# 2024-4T-MNT-2.net
KiCad netlist of a schematic drawn in EasyEDA Pro
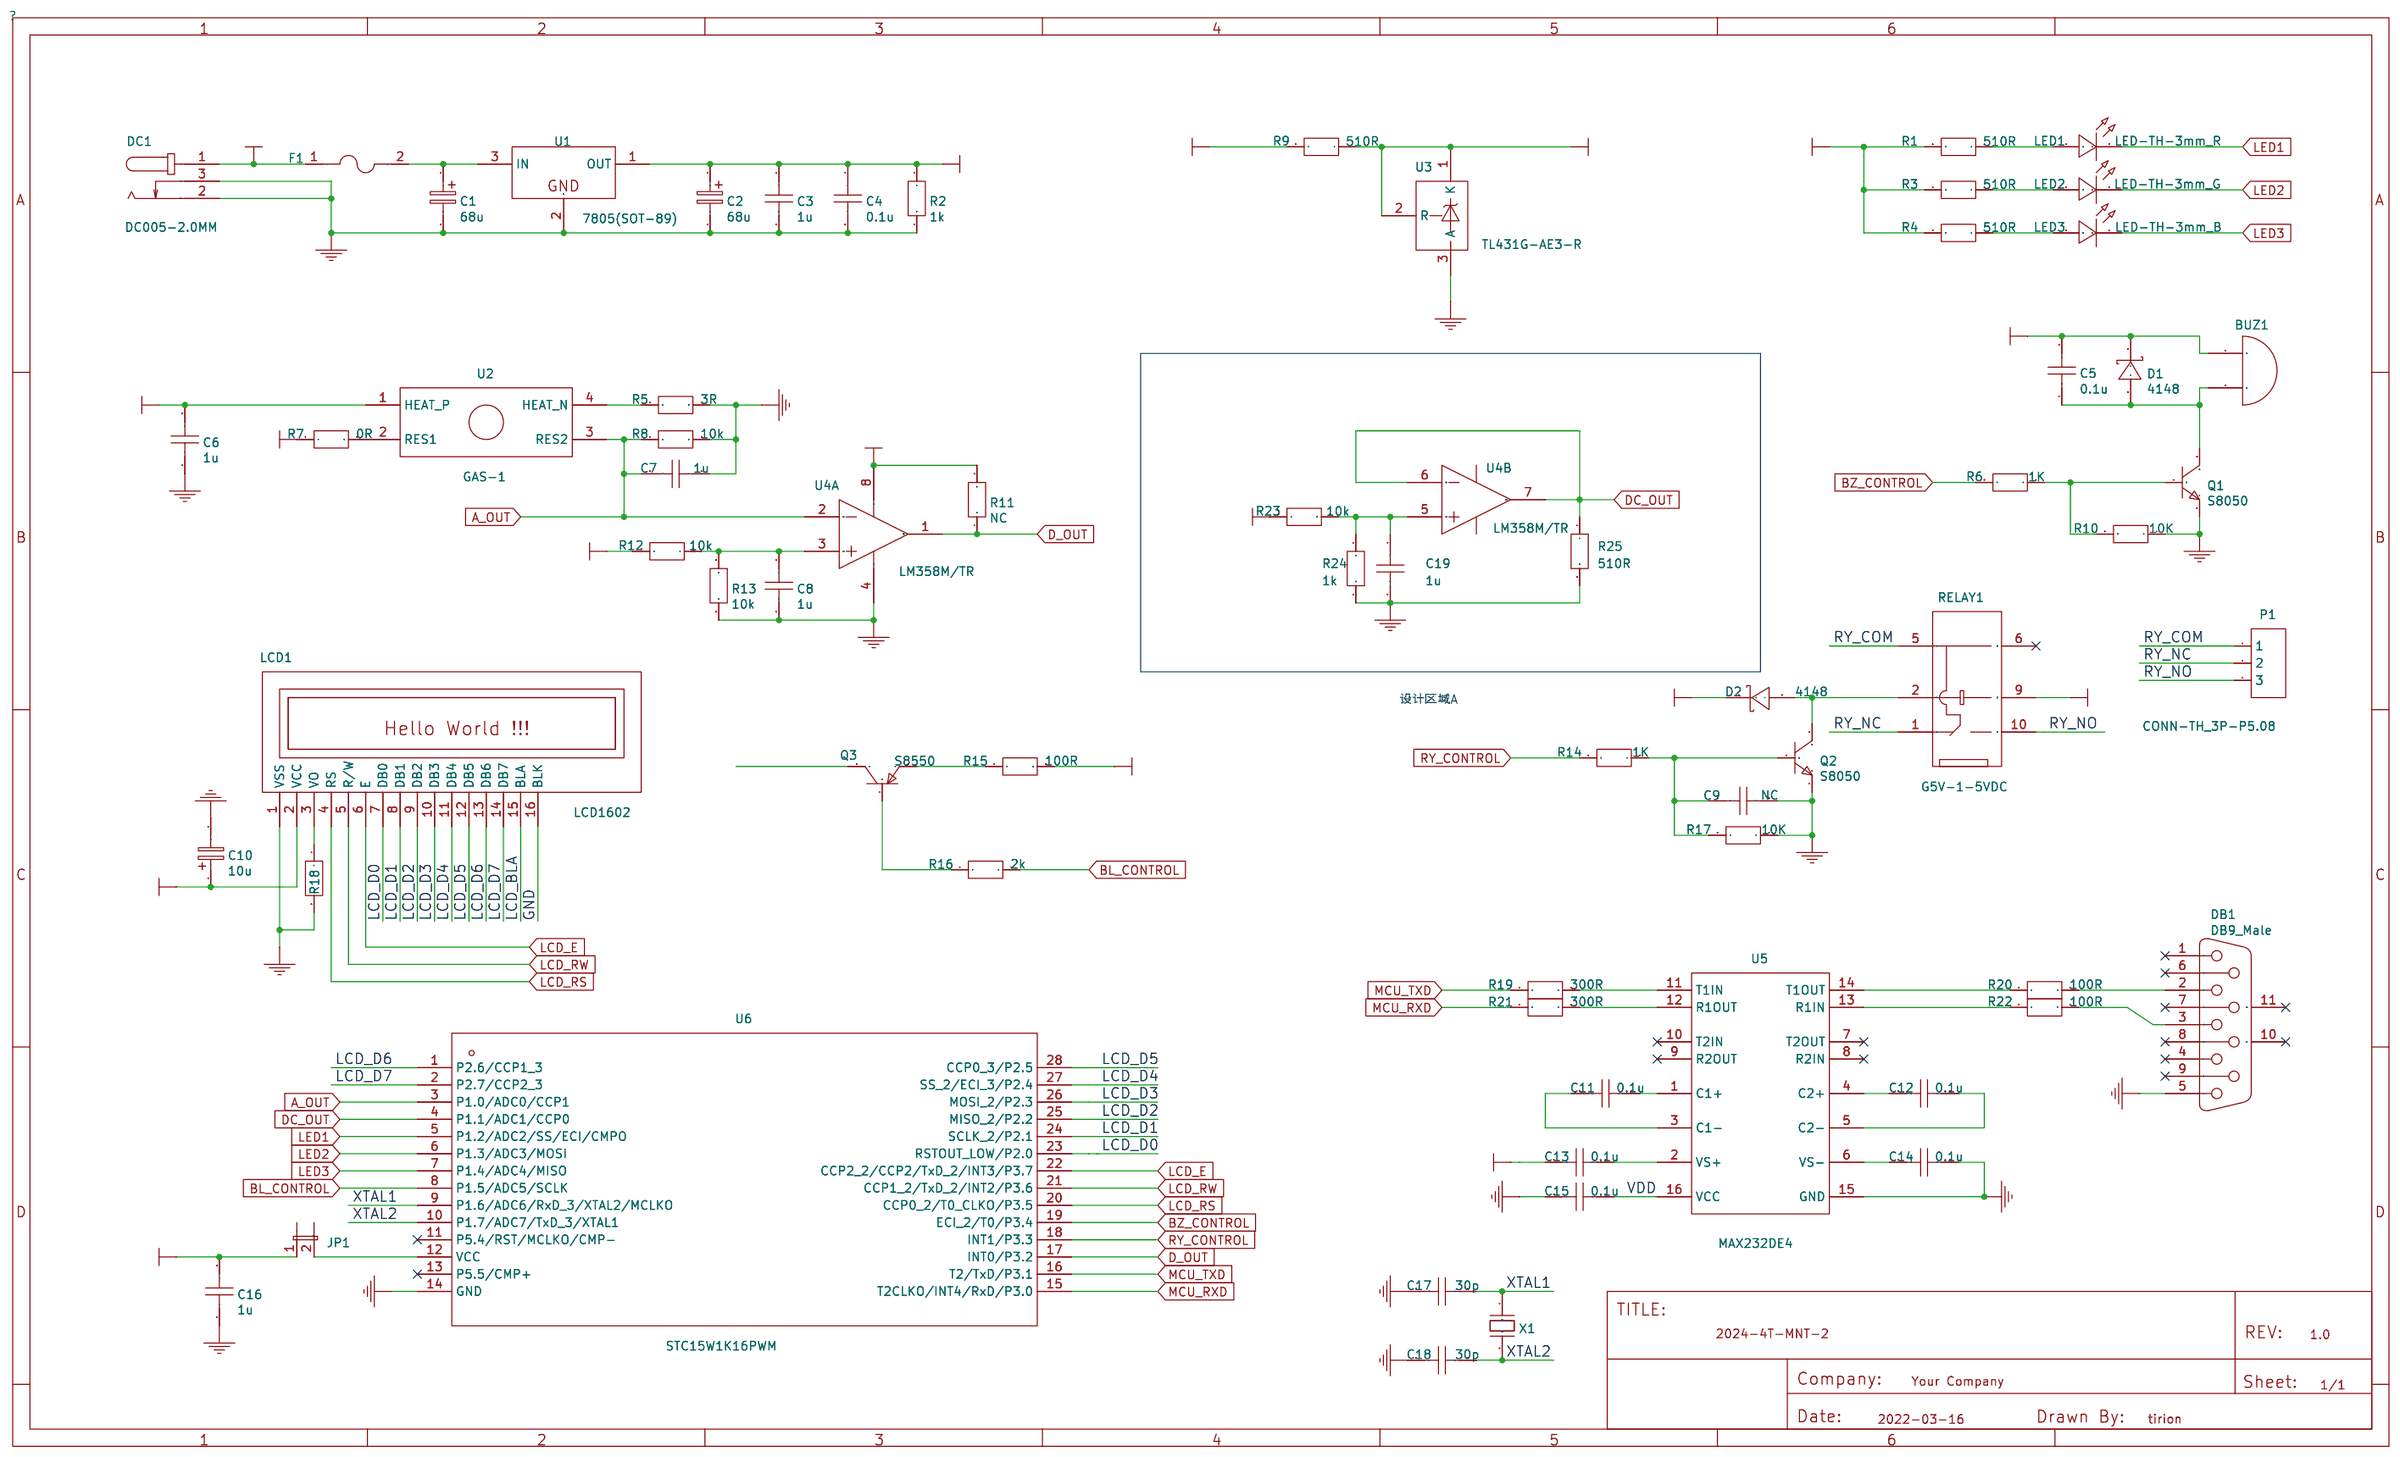
[diagram p0: schematic sheet]

(export (version "E")
  (design (tool "Eeschema 10.0.6"))
  (components
    (comp (ref "BUZ1") (value "BUZ1") (libsource (lib "easyedapro") (part "BUZ1")))
    (comp (ref "C1") (value "68u") (libsource (lib "easyedapro") (part "68u")))
    (comp (ref "C2") (value "68u") (libsource (lib "easyedapro") (part "68u")))
    (comp (ref "C3") (value "1u") (libsource (lib "easyedapro") (part "1u")))
    (comp (ref "C4") (value "0.1u") (libsource (lib "easyedapro") (part "0.1u")))
    (comp (ref "C5") (value "0.1u") (libsource (lib "easyedapro") (part "0.1u")))
    (comp (ref "C6") (value "1u") (libsource (lib "easyedapro") (part "1u")))
    (comp (ref "C7") (value "1u") (libsource (lib "easyedapro") (part "1u")))
    (comp (ref "C8") (value "1u") (libsource (lib "easyedapro") (part "1u")))
    (comp (ref "C9") (value "NC") (libsource (lib "") (part "NC_1")))
    (comp (ref "C10") (value "10u") (libsource (lib "easyedapro") (part "10u")))
    (comp (ref "C11") (value "0.1u") (libsource (lib "easyedapro") (part "0.1u")))
    (comp (ref "C12") (value "0.1u") (libsource (lib "easyedapro") (part "0.1u")))
    (comp (ref "C13") (value "0.1u") (libsource (lib "easyedapro") (part "0.1u")))
    (comp (ref "C14") (value "0.1u") (libsource (lib "easyedapro") (part "0.1u")))
    (comp (ref "C15") (value "0.1u") (libsource (lib "easyedapro") (part "0.1u")))
    (comp (ref "C16") (value "1u") (libsource (lib "easyedapro") (part "1u")))
    (comp (ref "C17") (value "30p") (libsource (lib "easyedapro") (part "30p")))
    (comp (ref "C18") (value "30p") (libsource (lib "easyedapro") (part "30p")))
    (comp (ref "C19") (value "1u") (libsource (lib "easyedapro") (part "1u")))
    (comp (ref "D1")
      (value "4148")
      (fields (field (name "Manufacturer Part") "SS14") (field (name "Manufacturer") "MDD"))
      (libsource (lib "easyedapro") (part "4148"))
    )
    (comp (ref "D2")
      (value "4148")
      (fields (field (name "Manufacturer Part") "SS14") (field (name "Manufacturer") "MDD"))
      (libsource (lib "easyedapro") (part "4148"))
    )
    (comp (ref "DB1")
      (value "DB9_Male")
      (fields (field (name "Manufacturer") "Amphenol"))
      (libsource (lib "easyedapro") (part "DB9_Male"))
    )
    (comp (ref "DC1")
      (value "DC005-2.0MM")
      (fields (field (name "Manufacturer") "SOFNG"))
      (libsource (lib "easyedapro") (part "DC005-2.0MM"))
    )
    (comp (ref "F1") (value "FUSE_F1812_FUSE") (libsource (lib "easyedapro") (part "FUSE_F1812_FUSE")))
    (comp (ref "JP1") (value "JUMPER2") (libsource (lib "easyedapro") (part "JUMPER2")))
    (comp (ref "LCD1")
      (value "LCD1602")
      (fields
        (field (name "Manufacturer Part") "LCM1602K-NSW-BBW")
        (field (name "Manufacturer") "LONTECH(厦门龙特)")
      )
      (libsource (lib "easyedapro") (part "LCD1602"))
    )
    (comp (ref "LED1")
      (value "LED-TH-3mm_R")
      (fields
        (field (name "Manufacturer Part") "204-10SDRD/S530-A3-L")
        (field (name "Manufacturer") "EVERLIGHT(台湾亿光)")
      )
      (libsource (lib "easyedapro") (part "LED-TH-3mm_R"))
    )
    (comp (ref "LED2")
      (value "LED-TH-3mm_G")
      (fields
        (field (name "Manufacturer Part") "204-10SYGD/S530-E3")
        (field (name "Manufacturer") "EVERLIGHT(台湾亿光)")
      )
      (libsource (lib "easyedapro") (part "LED-TH-3mm_G"))
    )
    (comp (ref "LED3")
      (value "LED-TH-3mm_B")
      (fields
        (field (name "Manufacturer Part") "204-10SUBC/S400-A4")
        (field (name "Manufacturer") "EVERLIGHT(台湾亿光)")
      )
      (libsource (lib "easyedapro") (part "LED-TH-3mm_B"))
    )
    (comp (ref "P1") (value "CONN-TH_3P-P5.08") (libsource (lib "easyedapro") (part "CONN-TH_3P-P5.08")))
    (comp (ref "Q1")
      (value "S8050")
      (fields (field (name "Manufacturer") "JSMSEMI"))
      (libsource (lib "easyedapro") (part "S8050"))
    )
    (comp (ref "Q2")
      (value "S8050")
      (fields (field (name "Manufacturer") "JSMSEMI"))
      (libsource (lib "easyedapro") (part "S8050"))
    )
    (comp (ref "Q3")
      (value "S8550")
      (fields
        (field (name "Manufacturer Part") "S8550-H")
        (field (name "Manufacturer") "Yangzhou Yangjie Elec Tech")
      )
      (libsource (lib "easyedapro") (part "S8550"))
    )
    (comp (ref "R1") (value "510R") (libsource (lib "easyedapro") (part "510R")))
    (comp (ref "R2") (value "1k") (libsource (lib "easyedapro") (part "1k")))
    (comp (ref "R3") (value "510R") (libsource (lib "easyedapro") (part "510R")))
    (comp (ref "R4") (value "510R") (libsource (lib "easyedapro") (part "510R")))
    (comp (ref "R5") (value "3R") (libsource (lib "easyedapro") (part "3R")))
    (comp (ref "R6") (value "1K") (libsource (lib "easyedapro") (part "1K")))
    (comp (ref "R7") (value "0R") (libsource (lib "easyedapro") (part "0R")))
    (comp (ref "R8") (value "10k") (libsource (lib "easyedapro") (part "10k")))
    (comp (ref "R9") (value "510R") (libsource (lib "easyedapro") (part "510R")))
    (comp (ref "R10") (value "10K") (libsource (lib "easyedapro") (part "10K")))
    (comp (ref "R11") (value "NC") (libsource (lib "easyedapro") (part "NC")))
    (comp (ref "R12") (value "10k") (libsource (lib "easyedapro") (part "10k")))
    (comp (ref "R13") (value "10k") (libsource (lib "easyedapro") (part "10k")))
    (comp (ref "R14") (value "1K") (libsource (lib "easyedapro") (part "1K")))
    (comp (ref "R15") (value "100R") (libsource (lib "easyedapro") (part "100R")))
    (comp (ref "R16") (value "2k") (libsource (lib "easyedapro") (part "2k")))
    (comp (ref "R17") (value "10K") (libsource (lib "easyedapro") (part "10K")))
    (comp (ref "R18") (value "10k") (libsource (lib "easyedapro") (part "10k")))
    (comp (ref "R19") (value "300R") (libsource (lib "easyedapro") (part "300R")))
    (comp (ref "R20") (value "100R") (libsource (lib "easyedapro") (part "100R")))
    (comp (ref "R21") (value "300R") (libsource (lib "easyedapro") (part "300R")))
    (comp (ref "R22") (value "100R") (libsource (lib "easyedapro") (part "100R")))
    (comp (ref "R23") (value "10k") (libsource (lib "easyedapro") (part "10k")))
    (comp (ref "R24") (value "1k") (libsource (lib "easyedapro") (part "1k")))
    (comp (ref "R25") (value "510R") (libsource (lib "easyedapro") (part "510R")))
    (comp (ref "RELAY1")
      (value "G5V-1-5VDC")
      (fields (field (name "Manufacturer") "OMRON"))
      (libsource (lib "easyedapro") (part "G5V-1-5VDC"))
    )
    (comp (ref "U1")
      (value "7805(SOT-89)")
      (fields (field (name "Manufacturer Part") "CJ78L05") (field (name "Manufacturer") "CJ"))
      (libsource (lib "easyedapro") (part "7805(SOT-89)"))
    )
    (comp (ref "U2") (value "GAS-1") (libsource (lib "easyedapro") (part "GAS-1")))
    (comp (ref "U3")
      (value "TL431G-AE3-R")
      (fields (field (name "Manufacturer") "UTC"))
      (libsource (lib "easyedapro") (part "TL431G-AE3-R"))
    )
    (comp (ref "U4")
      (value "LM358M/TR")
      (fields (field (name "Manufacturer") "HGSEMI"))
      (libsource (lib "easyedapro") (part "LM358M/TR"))
    )
    (comp (ref "U5") (value "MAX232DE4") (libsource (lib "easyedapro") (part "MAX232DE4")))
    (comp (ref "U6")
      (value "STC15W1K16PWM")
      (fields (field (name "Manufacturer") "STC"))
      (libsource (lib "easyedapro") (part "STC15W1K16PWM"))
    )
    (comp (ref "X1")
      (value "12MHZ")
      (fields (field (name "Manufacturer Part") "X49UD12MSD2SC") (field (name "Manufacturer") "LCSC"))
      (libsource (lib "easyedapro") (part "12MHZ"))
    )
  )
  (nets
    (net (code "1") (name "/LCD_BLA") (class "Default")
      (node (ref "LCD1") (pin "15") (pinfunction "BLA_15") (pintype "input"))
    )
    (net (code "2") (name "/LCD_D0") (class "Default")
      (node (ref "LCD1") (pin "7") (pinfunction "DB0_7") (pintype "input"))
      (node (ref "U6") (pin "23") (pinfunction "RSTOUT_LOW/P2.0_23") (pintype "input"))
    )
    (net (code "3") (name "/LCD_D1") (class "Default")
      (node (ref "LCD1") (pin "8") (pinfunction "DB1_8") (pintype "input"))
      (node (ref "U6") (pin "24") (pinfunction "SCLK_2/P2.1_24") (pintype "input"))
    )
    (net (code "4") (name "/LCD_D2") (class "Default")
      (node (ref "LCD1") (pin "9") (pinfunction "DB2_9") (pintype "input"))
      (node (ref "U6") (pin "25") (pinfunction "MISO_2/P2.2_25") (pintype "input"))
    )
    (net (code "5") (name "/LCD_D3") (class "Default")
      (node (ref "LCD1") (pin "10") (pinfunction "DB3_10") (pintype "input"))
      (node (ref "U6") (pin "26") (pinfunction "MOSI_2/P2.3_26") (pintype "input"))
    )
    (net (code "6") (name "/LCD_D4") (class "Default")
      (node (ref "LCD1") (pin "11") (pinfunction "DB4_11") (pintype "input"))
      (node (ref "U6") (pin "27") (pinfunction "SS_2/ECI_3/P2.4_27") (pintype "input"))
    )
    (net (code "7") (name "/LCD_D5") (class "Default")
      (node (ref "LCD1") (pin "12") (pinfunction "DB5_12") (pintype "input"))
      (node (ref "U6") (pin "28") (pinfunction "CCP0_3/P2.5_28") (pintype "input"))
    )
    (net (code "8") (name "/LCD_D6") (class "Default")
      (node (ref "LCD1") (pin "13") (pinfunction "DB6_13") (pintype "input"))
      (node (ref "U6") (pin "1") (pinfunction "P2.6/CCP1_3_1") (pintype "input"))
    )
    (net (code "9") (name "/LCD_D7") (class "Default")
      (node (ref "LCD1") (pin "14") (pinfunction "DB7_14") (pintype "input"))
      (node (ref "U6") (pin "2") (pinfunction "P2.7/CCP2_3_2") (pintype "input"))
    )
    (net (code "10") (name "/RY_COM") (class "Default")
      (node (ref "P1") (pin "1") (pinfunction "1_1") (pintype "input"))
      (node (ref "RELAY1") (pin "5") (pinfunction "5_5") (pintype "input"))
    )
    (net (code "11") (name "/RY_NC") (class "Default")
      (node (ref "P1") (pin "2") (pinfunction "2_2") (pintype "input"))
      (node (ref "RELAY1") (pin "1") (pinfunction "1_1") (pintype "input"))
    )
    (net (code "12") (name "/RY_NO") (class "Default")
      (node (ref "P1") (pin "3") (pinfunction "3_3") (pintype "input"))
      (node (ref "RELAY1") (pin "10") (pinfunction "10_10") (pintype "input"))
    )
    (net (code "13") (name "/XTAL1") (class "Default")
      (node (ref "C17") (pin "1") (pinfunction "1_1") (pintype "input"))
      (node (ref "U6") (pin "9") (pinfunction "P1.6/ADC6/RxD_3/XTAL2/MCLKO_9") (pintype "input"))
      (node (ref "X1") (pin "1") (pinfunction "OSC1_1") (pintype "input"))
    )
    (net (code "14") (name "/XTAL2") (class "Default")
      (node (ref "C18") (pin "1") (pinfunction "1_1") (pintype "input"))
      (node (ref "U6") (pin "10") (pinfunction "P1.7/ADC7/TxD_3/XTAL1_10") (pintype "input"))
      (node (ref "X1") (pin "2") (pinfunction "OSC2_2") (pintype "input"))
    )
    (net (code "15") (name "A_OUT") (class "Default")
      (node (ref "C7") (pin "2") (pinfunction "2_2") (pintype "input"))
      (node (ref "R8") (pin "1") (pinfunction "1_1") (pintype "input"))
      (node (ref "U2") (pin "3") (pinfunction "RES2_3") (pintype "input"))
      (node (ref "U4") (pin "2") (pinfunction "1IN-_2") (pintype "input"))
      (node (ref "U6") (pin "3") (pinfunction "P1.0/ADC0/CCP1_3") (pintype "input"))
    )
    (net (code "16") (name "BL_CONTROL") (class "Default")
      (node (ref "R16") (pin "2") (pinfunction "2_2") (pintype "input"))
      (node (ref "U6") (pin "8") (pinfunction "P1.5/ADC5/SCLK_8") (pintype "input"))
    )
    (net (code "17") (name "BZ_CONTROL") (class "Default")
      (node (ref "R6") (pin "2") (pinfunction "2_2") (pintype "input"))
      (node (ref "U6") (pin "19") (pinfunction "ECI_2/T0/P3.4_19") (pintype "input"))
    )
    (net (code "18") (name "DC_IN") (class "Default")
      (node (ref "DC1") (pin "1") (pinfunction "1_1") (pintype "input"))
      (node (ref "F1") (pin "1") (pinfunction "1_1") (pintype "input"))
      (node (ref "R23") (pin "2") (pinfunction "2_2") (pintype "input"))
    )
    (net (code "19") (name "DC_OUT") (class "Default")
      (node (ref "R25") (pin "1") (pinfunction "1_1") (pintype "input"))
      (node (ref "U4") (pin "6") (pinfunction "2IN-_6") (pintype "input"))
      (node (ref "U4") (pin "7") (pinfunction "2OUT_7") (pintype "output"))
      (node (ref "U6") (pin "4") (pinfunction "P1.1/ADC1/CCP0_4") (pintype "input"))
    )
    (net (code "20") (name "D_OUT") (class "Default")
      (node (ref "R11") (pin "1") (pinfunction "1_1") (pintype "input"))
      (node (ref "U4") (pin "1") (pinfunction "1OUT_1") (pintype "output"))
      (node (ref "U6") (pin "17") (pinfunction "INT0/P3.2_17") (pintype "input"))
    )
    (net (code "21") (name "GND") (class "Default")
      (node (ref "C1") (pin "2") (pinfunction "2_2") (pintype "input"))
      (node (ref "C10") (pin "2") (pinfunction "2_2") (pintype "input"))
      (node (ref "C14") (pin "2") (pinfunction "2_2") (pintype "input"))
      (node (ref "C15") (pin "1") (pinfunction "1_1") (pintype "input"))
      (node (ref "C16") (pin "1") (pinfunction "1_1") (pintype "input"))
      (node (ref "C17") (pin "2") (pinfunction "2_2") (pintype "input"))
      (node (ref "C18") (pin "2") (pinfunction "2_2") (pintype "input"))
      (node (ref "C19") (pin "2") (pinfunction "2_2") (pintype "input"))
      (node (ref "C2") (pin "2") (pinfunction "2_2") (pintype "input"))
      (node (ref "C3") (pin "2") (pinfunction "2_2") (pintype "input"))
      (node (ref "C4") (pin "2") (pinfunction "2_2") (pintype "input"))
      (node (ref "C6") (pin "1") (pinfunction "1_1") (pintype "input"))
      (node (ref "C7") (pin "1") (pinfunction "1_1") (pintype "input"))
      (node (ref "C8") (pin "2") (pinfunction "2_2") (pintype "input"))
      (node (ref "C9") (pin "2") (pinfunction "2_2") (pintype "input"))
      (node (ref "DB1") (pin "5") (pinfunction "5_5") (pintype "input"))
      (node (ref "DC1") (pin "2") (pinfunction "2_2") (pintype "input"))
      (node (ref "DC1") (pin "3") (pinfunction "3_3") (pintype "input"))
      (node (ref "LCD1") (pin "1") (pinfunction "VSS_1") (pintype "input"))
      (node (ref "LCD1") (pin "16") (pinfunction "BLK_16") (pintype "input"))
      (node (ref "Q1") (pin "2") (pinfunction "E_2") (pintype "input"))
      (node (ref "Q2") (pin "2") (pinfunction "E_2") (pintype "input"))
      (node (ref "R10") (pin "1") (pinfunction "1_1") (pintype "input"))
      (node (ref "R13") (pin "2") (pinfunction "2_2") (pintype "input"))
      (node (ref "R17") (pin "1") (pinfunction "1_1") (pintype "input"))
      (node (ref "R18") (pin "2") (pinfunction "2_2") (pintype "input"))
      (node (ref "R2") (pin "2") (pinfunction "2_2") (pintype "input"))
      (node (ref "R24") (pin "2") (pinfunction "2_2") (pintype "input"))
      (node (ref "R25") (pin "2") (pinfunction "2_2") (pintype "input"))
      (node (ref "R5") (pin "2") (pinfunction "2_2") (pintype "input"))
      (node (ref "R8") (pin "2") (pinfunction "2_2") (pintype "input"))
      (node (ref "U1") (pin "2") (pinfunction "GND_2") (pintype "input"))
      (node (ref "U3") (pin "3") (pinfunction "A_3") (pintype "input"))
      (node (ref "U4") (pin "4") (pinfunction "GND_4") (pintype "input"))
      (node (ref "U5") (pin "15") (pinfunction "GND_15") (pintype "input"))
      (node (ref "U6") (pin "14") (pinfunction "GND_14") (pintype "input"))
    )
    (net (code "22") (name "LCD_E") (class "Default")
      (node (ref "LCD1") (pin "6") (pinfunction "E_6") (pintype "input"))
      (node (ref "U6") (pin "22") (pinfunction "CCP2_2/CCP2/TxD_2/INT3/P3.7_22") (pintype "input"))
    )
    (net (code "23") (name "LCD_RS") (class "Default")
      (node (ref "LCD1") (pin "4") (pinfunction "RS_4") (pintype "input"))
      (node (ref "U6") (pin "20") (pinfunction "CCP0_2/T0_CLKO/P3.5_20") (pintype "input"))
    )
    (net (code "24") (name "LCD_RW") (class "Default")
      (node (ref "LCD1") (pin "5") (pinfunction "R/W_5") (pintype "input"))
      (node (ref "U6") (pin "21") (pinfunction "CCP1_2/TxD_2/INT2/P3.6_21") (pintype "input"))
    )
    (net (code "25") (name "LED1") (class "Default")
      (node (ref "LED1") (pin "2") (pinfunction "2_2") (pintype "input"))
      (node (ref "U6") (pin "5") (pinfunction "P1.2/ADC2/SS/ECI/CMPO_5") (pintype "input"))
    )
    (net (code "26") (name "LED2") (class "Default")
      (node (ref "LED2") (pin "2") (pinfunction "2_2") (pintype "input"))
      (node (ref "U6") (pin "6") (pinfunction "P1.3/ADC3/MOSI_6") (pintype "input"))
    )
    (net (code "27") (name "LED3") (class "Default")
      (node (ref "LED3") (pin "2") (pinfunction "2_2") (pintype "input"))
      (node (ref "U6") (pin "7") (pinfunction "P1.4/ADC4/MISO_7") (pintype "input"))
    )
    (net (code "28") (name "MCU_RXD") (class "Default")
      (node (ref "R21") (pin "1") (pinfunction "1_1") (pintype "input"))
      (node (ref "U6") (pin "15") (pinfunction "T2CLKO/INT4/RxD/P3.0_15") (pintype "input"))
    )
    (net (code "29") (name "MCU_TXD") (class "Default")
      (node (ref "R19") (pin "1") (pinfunction "1_1") (pintype "input"))
      (node (ref "U6") (pin "16") (pinfunction "T2/TxD/P3.1_16") (pintype "input"))
    )
    (net (code "30") (name "Net-(BUZ1-B)") (class "Default")
      (node (ref "BUZ1") (pin "2") (pinfunction "B_2") (pintype "input"))
      (node (ref "C5") (pin "1") (pinfunction "1_1") (pintype "input"))
      (node (ref "D1") (pin "2") (pinfunction "A_2") (pintype "input"))
      (node (ref "Q1") (pin "3") (pinfunction "C_3") (pintype "input"))
    )
    (net (code "31") (name "Net-(D2-A)") (class "Default")
      (node (ref "D2") (pin "2") (pinfunction "A_2") (pintype "input"))
      (node (ref "Q2") (pin "3") (pinfunction "C_3") (pintype "input"))
      (node (ref "RELAY1") (pin "2") (pinfunction "2_2") (pintype "input"))
    )
    (net (code "32") (name "Net-(DB1-Pad2)") (class "Default")
      (node (ref "DB1") (pin "2") (pinfunction "2_2") (pintype "input"))
      (node (ref "R20") (pin "2") (pinfunction "2_2") (pintype "input"))
    )
    (net (code "33") (name "Net-(DB1-Pad3)") (class "Default")
      (node (ref "DB1") (pin "3") (pinfunction "3_3") (pintype "input"))
      (node (ref "R22") (pin "2") (pinfunction "2_2") (pintype "input"))
    )
    (net (code "34") (name "Net-(LCD1-VO)") (class "Default")
      (node (ref "LCD1") (pin "3") (pinfunction "VO_3") (pintype "input"))
      (node (ref "R18") (pin "1") (pinfunction "1_1") (pintype "input"))
    )
    (net (code "35") (name "Net-(LED1-Pad1)") (class "Default")
      (node (ref "LED1") (pin "1") (pinfunction "1_1") (pintype "input"))
      (node (ref "R1") (pin "1") (pinfunction "1_1") (pintype "input"))
    )
    (net (code "36") (name "Net-(LED2-Pad1)") (class "Default")
      (node (ref "LED2") (pin "1") (pinfunction "1_1") (pintype "input"))
      (node (ref "R3") (pin "1") (pinfunction "1_1") (pintype "input"))
    )
    (net (code "37") (name "Net-(LED3-Pad1)") (class "Default")
      (node (ref "LED3") (pin "1") (pinfunction "1_1") (pintype "input"))
      (node (ref "R4") (pin "1") (pinfunction "1_1") (pintype "input"))
    )
    (net (code "38") (name "Net-(Q1-B)") (class "Default")
      (node (ref "Q1") (pin "1") (pinfunction "B_1") (pintype "input"))
      (node (ref "R10") (pin "2") (pinfunction "2_2") (pintype "input"))
      (node (ref "R6") (pin "1") (pinfunction "1_1") (pintype "input"))
    )
    (net (code "39") (name "Net-(Q2-B)") (class "Default")
      (node (ref "C9") (pin "1") (pinfunction "1_1") (pintype "input"))
      (node (ref "Q2") (pin "1") (pinfunction "B_1") (pintype "input"))
      (node (ref "R14") (pin "1") (pinfunction "1_1") (pintype "input"))
      (node (ref "R17") (pin "2") (pinfunction "2_2") (pintype "input"))
    )
    (net (code "40") (name "Net-(Q3-B)") (class "Default")
      (node (ref "Q3") (pin "1") (pinfunction "B_1") (pintype "input"))
      (node (ref "R16") (pin "1") (pinfunction "1_1") (pintype "input"))
    )
    (net (code "41") (name "Net-(Q3-E)") (class "Default")
      (node (ref "Q3") (pin "2") (pinfunction "E_2") (pintype "input"))
      (node (ref "R15") (pin "1") (pinfunction "1_1") (pintype "input"))
    )
    (net (code "42") (name "Net-(U1-IN)") (class "Default")
      (node (ref "C1") (pin "1") (pinfunction "1_1") (pintype "input"))
      (node (ref "F1") (pin "2") (pinfunction "2_2") (pintype "input"))
      (node (ref "U1") (pin "3") (pinfunction "IN_3") (pintype "input"))
    )
    (net (code "43") (name "Net-(U2-HEAT_N)") (class "Default")
      (node (ref "R5") (pin "1") (pinfunction "1_1") (pintype "input"))
      (node (ref "U2") (pin "4") (pinfunction "HEAT_N_4") (pintype "input"))
    )
    (net (code "44") (name "Net-(U2-RES1)") (class "Default")
      (node (ref "R7") (pin "2") (pinfunction "2_2") (pintype "input"))
      (node (ref "U2") (pin "2") (pinfunction "RES1_2") (pintype "input"))
    )
    (net (code "45") (name "Net-(U4A-1IN+)") (class "Default")
      (node (ref "C8") (pin "1") (pinfunction "1_1") (pintype "input"))
      (node (ref "R12") (pin "1") (pinfunction "1_1") (pintype "input"))
      (node (ref "R13") (pin "1") (pinfunction "1_1") (pintype "input"))
      (node (ref "U4") (pin "3") (pinfunction "1IN+_3") (pintype "input"))
    )
    (net (code "46") (name "Net-(U4B-2IN+)") (class "Default")
      (node (ref "C19") (pin "1") (pinfunction "1_1") (pintype "input"))
      (node (ref "R23") (pin "1") (pinfunction "1_1") (pintype "input"))
      (node (ref "R24") (pin "1") (pinfunction "1_1") (pintype "input"))
      (node (ref "U4") (pin "5") (pinfunction "2IN+_5") (pintype "input"))
    )
    (net (code "47") (name "Net-(U5-C1+)") (class "Default")
      (node (ref "C11") (pin "2") (pinfunction "2_2") (pintype "input"))
      (node (ref "U5") (pin "1") (pinfunction "C1+_1") (pintype "input"))
    )
    (net (code "48") (name "Net-(U5-C1-)") (class "Default")
      (node (ref "C11") (pin "1") (pinfunction "1_1") (pintype "input"))
      (node (ref "U5") (pin "3") (pinfunction "C1-_3") (pintype "input"))
    )
    (net (code "49") (name "Net-(U5-C2+)") (class "Default")
      (node (ref "C12") (pin "1") (pinfunction "1_1") (pintype "input"))
      (node (ref "U5") (pin "4") (pinfunction "C2+_4") (pintype "input"))
    )
    (net (code "50") (name "Net-(U5-C2-)") (class "Default")
      (node (ref "C12") (pin "2") (pinfunction "2_2") (pintype "input"))
      (node (ref "U5") (pin "5") (pinfunction "C2-_5") (pintype "input"))
    )
    (net (code "51") (name "Net-(U5-R1IN)") (class "Default")
      (node (ref "R22") (pin "1") (pinfunction "1_1") (pintype "input"))
      (node (ref "U5") (pin "13") (pinfunction "R1IN_13") (pintype "input"))
    )
    (net (code "52") (name "Net-(U5-R1OUT)") (class "Default")
      (node (ref "R21") (pin "2") (pinfunction "2_2") (pintype "input"))
      (node (ref "U5") (pin "12") (pinfunction "R1OUT_12") (pintype "output"))
    )
    (net (code "53") (name "Net-(U5-T1IN)") (class "Default")
      (node (ref "R19") (pin "2") (pinfunction "2_2") (pintype "input"))
      (node (ref "U5") (pin "11") (pinfunction "T1IN_11") (pintype "input"))
    )
    (net (code "54") (name "Net-(U5-T1OUT)") (class "Default")
      (node (ref "R20") (pin "1") (pinfunction "1_1") (pintype "input"))
      (node (ref "U5") (pin "14") (pinfunction "T1OUT_14") (pintype "output"))
    )
    (net (code "55") (name "Net-(U5-VS+)") (class "Default")
      (node (ref "C13") (pin "2") (pinfunction "2_2") (pintype "input"))
      (node (ref "U5") (pin "2") (pinfunction "VS+_2") (pintype "input"))
    )
    (net (code "56") (name "Net-(U5-VS-)") (class "Default")
      (node (ref "C14") (pin "1") (pinfunction "1_1") (pintype "input"))
      (node (ref "U5") (pin "6") (pinfunction "VS-_6") (pintype "input"))
    )
    (net (code "57") (name "Net-(U6-VCC)") (class "Default")
      (node (ref "JP1") (pin "2") (pinfunction "2_2") (pintype "input"))
      (node (ref "U6") (pin "12") (pinfunction "VCC_12") (pintype "input"))
    )
    (net (code "58") (name "RY_CONTROL") (class "Default")
      (node (ref "R14") (pin "2") (pinfunction "2_2") (pintype "input"))
      (node (ref "U6") (pin "18") (pinfunction "INT1/P3.3_18") (pintype "input"))
    )
    (net (code "59") (name "VDD") (class "Default")
      (node (ref "BUZ1") (pin "1") (pinfunction "A_1") (pintype "input"))
      (node (ref "C10") (pin "1") (pinfunction "1_1") (pintype "input"))
      (node (ref "C13") (pin "1") (pinfunction "1_1") (pintype "input"))
      (node (ref "C15") (pin "2") (pinfunction "2_2") (pintype "input"))
      (node (ref "C16") (pin "2") (pinfunction "2_2") (pintype "input"))
      (node (ref "C2") (pin "1") (pinfunction "1_1") (pintype "input"))
      (node (ref "C3") (pin "1") (pinfunction "1_1") (pintype "input"))
      (node (ref "C4") (pin "1") (pinfunction "1_1") (pintype "input"))
      (node (ref "C5") (pin "2") (pinfunction "2_2") (pintype "input"))
      (node (ref "C6") (pin "2") (pinfunction "2_2") (pintype "input"))
      (node (ref "D1") (pin "1") (pinfunction "K_1") (pintype "input"))
      (node (ref "D2") (pin "1") (pinfunction "K_1") (pintype "input"))
      (node (ref "JP1") (pin "1") (pinfunction "1_1") (pintype "input"))
      (node (ref "LCD1") (pin "2") (pinfunction "VCC_2") (pintype "input"))
      (node (ref "R1") (pin "2") (pinfunction "2_2") (pintype "input"))
      (node (ref "R11") (pin "2") (pinfunction "2_2") (pintype "input"))
      (node (ref "R15") (pin "2") (pinfunction "2_2") (pintype "input"))
      (node (ref "R2") (pin "1") (pinfunction "1_1") (pintype "input"))
      (node (ref "R3") (pin "2") (pinfunction "2_2") (pintype "input"))
      (node (ref "R4") (pin "2") (pinfunction "2_2") (pintype "input"))
      (node (ref "R9") (pin "2") (pinfunction "2_2") (pintype "input"))
      (node (ref "RELAY1") (pin "9") (pinfunction "9_9") (pintype "input"))
      (node (ref "U1") (pin "1") (pinfunction "OUT_1") (pintype "input"))
      (node (ref "U2") (pin "1") (pinfunction "HEAT_P_1") (pintype "input"))
      (node (ref "U4") (pin "8") (pinfunction "VCC_8") (pintype "input"))
      (node (ref "U5") (pin "16") (pinfunction "VCC_16") (pintype "input"))
    )
    (net (code "60") (name "VREF") (class "Default")
      (node (ref "R12") (pin "2") (pinfunction "2_2") (pintype "input"))
      (node (ref "R7") (pin "1") (pinfunction "1_1") (pintype "input"))
      (node (ref "R9") (pin "1") (pinfunction "1_1") (pintype "input"))
      (node (ref "U3") (pin "1") (pinfunction "K_1") (pintype "input"))
      (node (ref "U3") (pin "2") (pinfunction "R_2") (pintype "input"))
    )
    (net (code "61") (name "unconnected-(DB1-MH1-Pad10)") (class "Default")
      (node (ref "DB1") (pin "10") (pinfunction "MH1_10") (pintype "input+no_connect"))
    )
    (net (code "62") (name "unconnected-(DB1-MH2-Pad11)") (class "Default")
      (node (ref "DB1") (pin "11") (pinfunction "MH2_11") (pintype "input+no_connect"))
    )
    (net (code "63") (name "unconnected-(DB1-Pad1)") (class "Default")
      (node (ref "DB1") (pin "1") (pinfunction "1_1") (pintype "input+no_connect"))
    )
    (net (code "64") (name "unconnected-(DB1-Pad4)") (class "Default")
      (node (ref "DB1") (pin "4") (pinfunction "4_4") (pintype "input+no_connect"))
    )
    (net (code "65") (name "unconnected-(DB1-Pad6)") (class "Default")
      (node (ref "DB1") (pin "6") (pinfunction "6_6") (pintype "input+no_connect"))
    )
    (net (code "66") (name "unconnected-(DB1-Pad7)") (class "Default")
      (node (ref "DB1") (pin "7") (pinfunction "7_7") (pintype "input+no_connect"))
    )
    (net (code "67") (name "unconnected-(DB1-Pad8)") (class "Default")
      (node (ref "DB1") (pin "8") (pinfunction "8_8") (pintype "input+no_connect"))
    )
    (net (code "68") (name "unconnected-(DB1-Pad9)") (class "Default")
      (node (ref "DB1") (pin "9") (pinfunction "9_9") (pintype "input+no_connect"))
    )
    (net (code "69") (name "unconnected-(Q3-C-Pad3)") (class "Default")
      (node (ref "Q3") (pin "3") (pinfunction "C_3") (pintype "input"))
    )
    (net (code "70") (name "unconnected-(RELAY1-Pad6)") (class "Default")
      (node (ref "RELAY1") (pin "6") (pinfunction "6_6") (pintype "input+no_connect"))
    )
    (net (code "71") (name "unconnected-(U5-R2IN-Pad8)") (class "Default")
      (node (ref "U5") (pin "8") (pinfunction "R2IN_8") (pintype "input+no_connect"))
    )
    (net (code "72") (name "unconnected-(U5-R2OUT-Pad9)") (class "Default")
      (node (ref "U5") (pin "9") (pinfunction "R2OUT_9") (pintype "output+no_connect"))
    )
    (net (code "73") (name "unconnected-(U5-T2IN-Pad10)") (class "Default")
      (node (ref "U5") (pin "10") (pinfunction "T2IN_10") (pintype "input+no_connect"))
    )
    (net (code "74") (name "unconnected-(U5-T2OUT-Pad7)") (class "Default")
      (node (ref "U5") (pin "7") (pinfunction "T2OUT_7") (pintype "output+no_connect"))
    )
    (net (code "75") (name "unconnected-(U6-P5.4{slash}RST{slash}MCLKO{slash}CMP--Pad11)") (class "Default")
      (node (ref "U6") (pin "11") (pinfunction "P5.4/RST/MCLKO/CMP-_11") (pintype "input+no_connect"))
    )
    (net (code "76") (name "unconnected-(U6-P5.5{slash}CMP+-Pad13)") (class "Default")
      (node (ref "U6") (pin "13") (pinfunction "P5.5/CMP+_13") (pintype "input+no_connect"))
    )
  )
)
